# Sheet1.net
KiCad netlist of a schematic drawn in Altium Designer
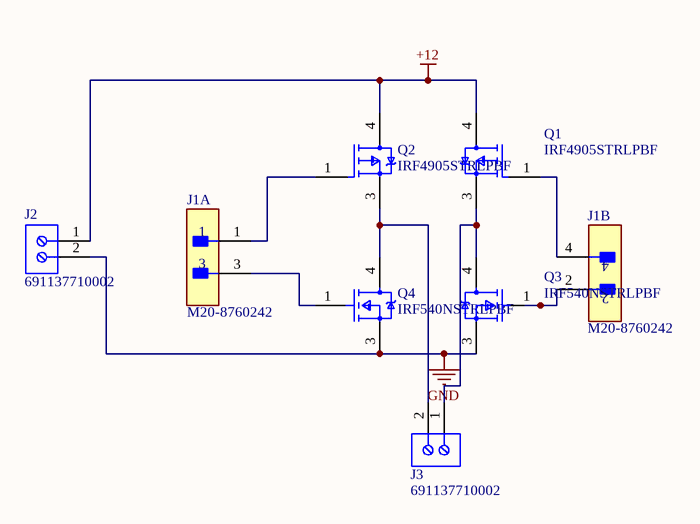
[diagram p0: Sheet1.SchDoc]

(export (version "E")
  (design (tool "Eeschema 10.0.6"))
  (components
    (comp (ref "J1")
      (value "M20-8760242")
      (footprint "FP-M20-8760242-MFG")
      (description "CONN HEADER SMD 4POS 2.54MM")
      (libsource (lib "") (part "1621473add15499e993d6bbd36d0f06_1"))
    )
    (comp (ref "J2")
      (value "691137710002")
      (footprint "691137710002")
      (libsource (lib "Altium Content Vault") (part "TBL - 1R - 02P - Screw"))
    )
    (comp (ref "J3")
      (value "691137710002")
      (footprint "691137710002")
      (libsource (lib "Altium Content Vault") (part "TBL - 1R - 02P - Screw"))
    )
    (comp (ref "Q1")
      (value "IRF4905STRLPBF")
      (footprint "FP-PG-TO263-3-MFG")
      (description "MOSFET P-CH 55V 42A D2PAK")
      (libsource (lib "Altium Content Vault") (part "a5278315d9cb221a74ee3a2ac99783a"))
    )
    (comp (ref "Q2")
      (value "IRF4905STRLPBF")
      (footprint "FP-PG-TO263-3-MFG")
      (description "MOSFET P-CH 55V 42A D2PAK")
      (libsource (lib "Altium Content Vault") (part "a5278315d9cb221a74ee3a2ac99783a"))
    )
    (comp (ref "Q3")
      (value "IRF540NSTRLPBF")
      (footprint "FP-PG-TO263-3-MFG")
      (description "IRF540NSTRLPBF Transistor MOSFET N Channel 100 Volt 33 Amp 3-Pin 2+ Tab D2pak Tape And Reel")
      (libsource (lib "Altium Content Vault") (part "880dca94e4e73acafd9c8cab4fdbffa"))
    )
    (comp (ref "Q4")
      (value "IRF540NSTRLPBF")
      (footprint "FP-PG-TO263-3-MFG")
      (description "IRF540NSTRLPBF Transistor MOSFET N Channel 100 Volt 33 Amp 3-Pin 2+ Tab D2pak Tape And Reel")
      (libsource (lib "Altium Content Vault") (part "880dca94e4e73acafd9c8cab4fdbffa"))
    )
  )
  (nets
    (net (code "1") (name "+12") (class "Default")
      (node (ref "J2") (pin "1") (pinfunction "1_1") (pintype "passive"))
      (node (ref "Q1") (pin "4") (pinfunction "D_4") (pintype "passive"))
      (node (ref "Q2") (pin "4") (pinfunction "D_4") (pintype "passive"))
    )
    (net (code "2") (name "GND") (class "Default")
      (node (ref "J2") (pin "2") (pinfunction "2_2") (pintype "passive"))
      (node (ref "Q3") (pin "3") (pinfunction "SOURCE_3") (pintype "passive"))
      (node (ref "Q4") (pin "3") (pinfunction "SOURCE_3") (pintype "passive"))
    )
    (net (code "3") (name "Net-(Q1-G)") (class "Default")
      (node (ref "J1") (pin "4") (pinfunction "4_4") (pintype "passive"))
      (node (ref "Q1") (pin "1") (pinfunction "G_1") (pintype "passive"))
    )
    (net (code "4") (name "Net-(Q1-S)") (class "Default")
      (node (ref "J3") (pin "1") (pinfunction "1_1") (pintype "passive"))
      (node (ref "Q1") (pin "3") (pinfunction "S_3") (pintype "passive"))
      (node (ref "Q3") (pin "4") (pinfunction "DRAIN_4") (pintype "passive"))
    )
    (net (code "5") (name "Net-(Q2-G)") (class "Default")
      (node (ref "J1") (pin "1") (pinfunction "1_1") (pintype "passive"))
      (node (ref "Q2") (pin "1") (pinfunction "G_1") (pintype "passive"))
    )
    (net (code "6") (name "Net-(Q2-S)") (class "Default")
      (node (ref "J3") (pin "2") (pinfunction "2_2") (pintype "passive"))
      (node (ref "Q2") (pin "3") (pinfunction "S_3") (pintype "passive"))
      (node (ref "Q4") (pin "4") (pinfunction "DRAIN_4") (pintype "passive"))
    )
    (net (code "7") (name "Net-(Q3-GATE)") (class "Default")
      (node (ref "J1") (pin "2") (pinfunction "2_2") (pintype "passive"))
      (node (ref "Q3") (pin "1") (pinfunction "GATE_1") (pintype "passive"))
    )
    (net (code "8") (name "Net-(Q4-GATE)") (class "Default")
      (node (ref "J1") (pin "3") (pinfunction "3_3") (pintype "passive"))
      (node (ref "Q4") (pin "1") (pinfunction "GATE_1") (pintype "passive"))
    )
  )
)
